# LED-PCB_DIG2.net
KiCad netlist of a schematic drawn in Altium Designer
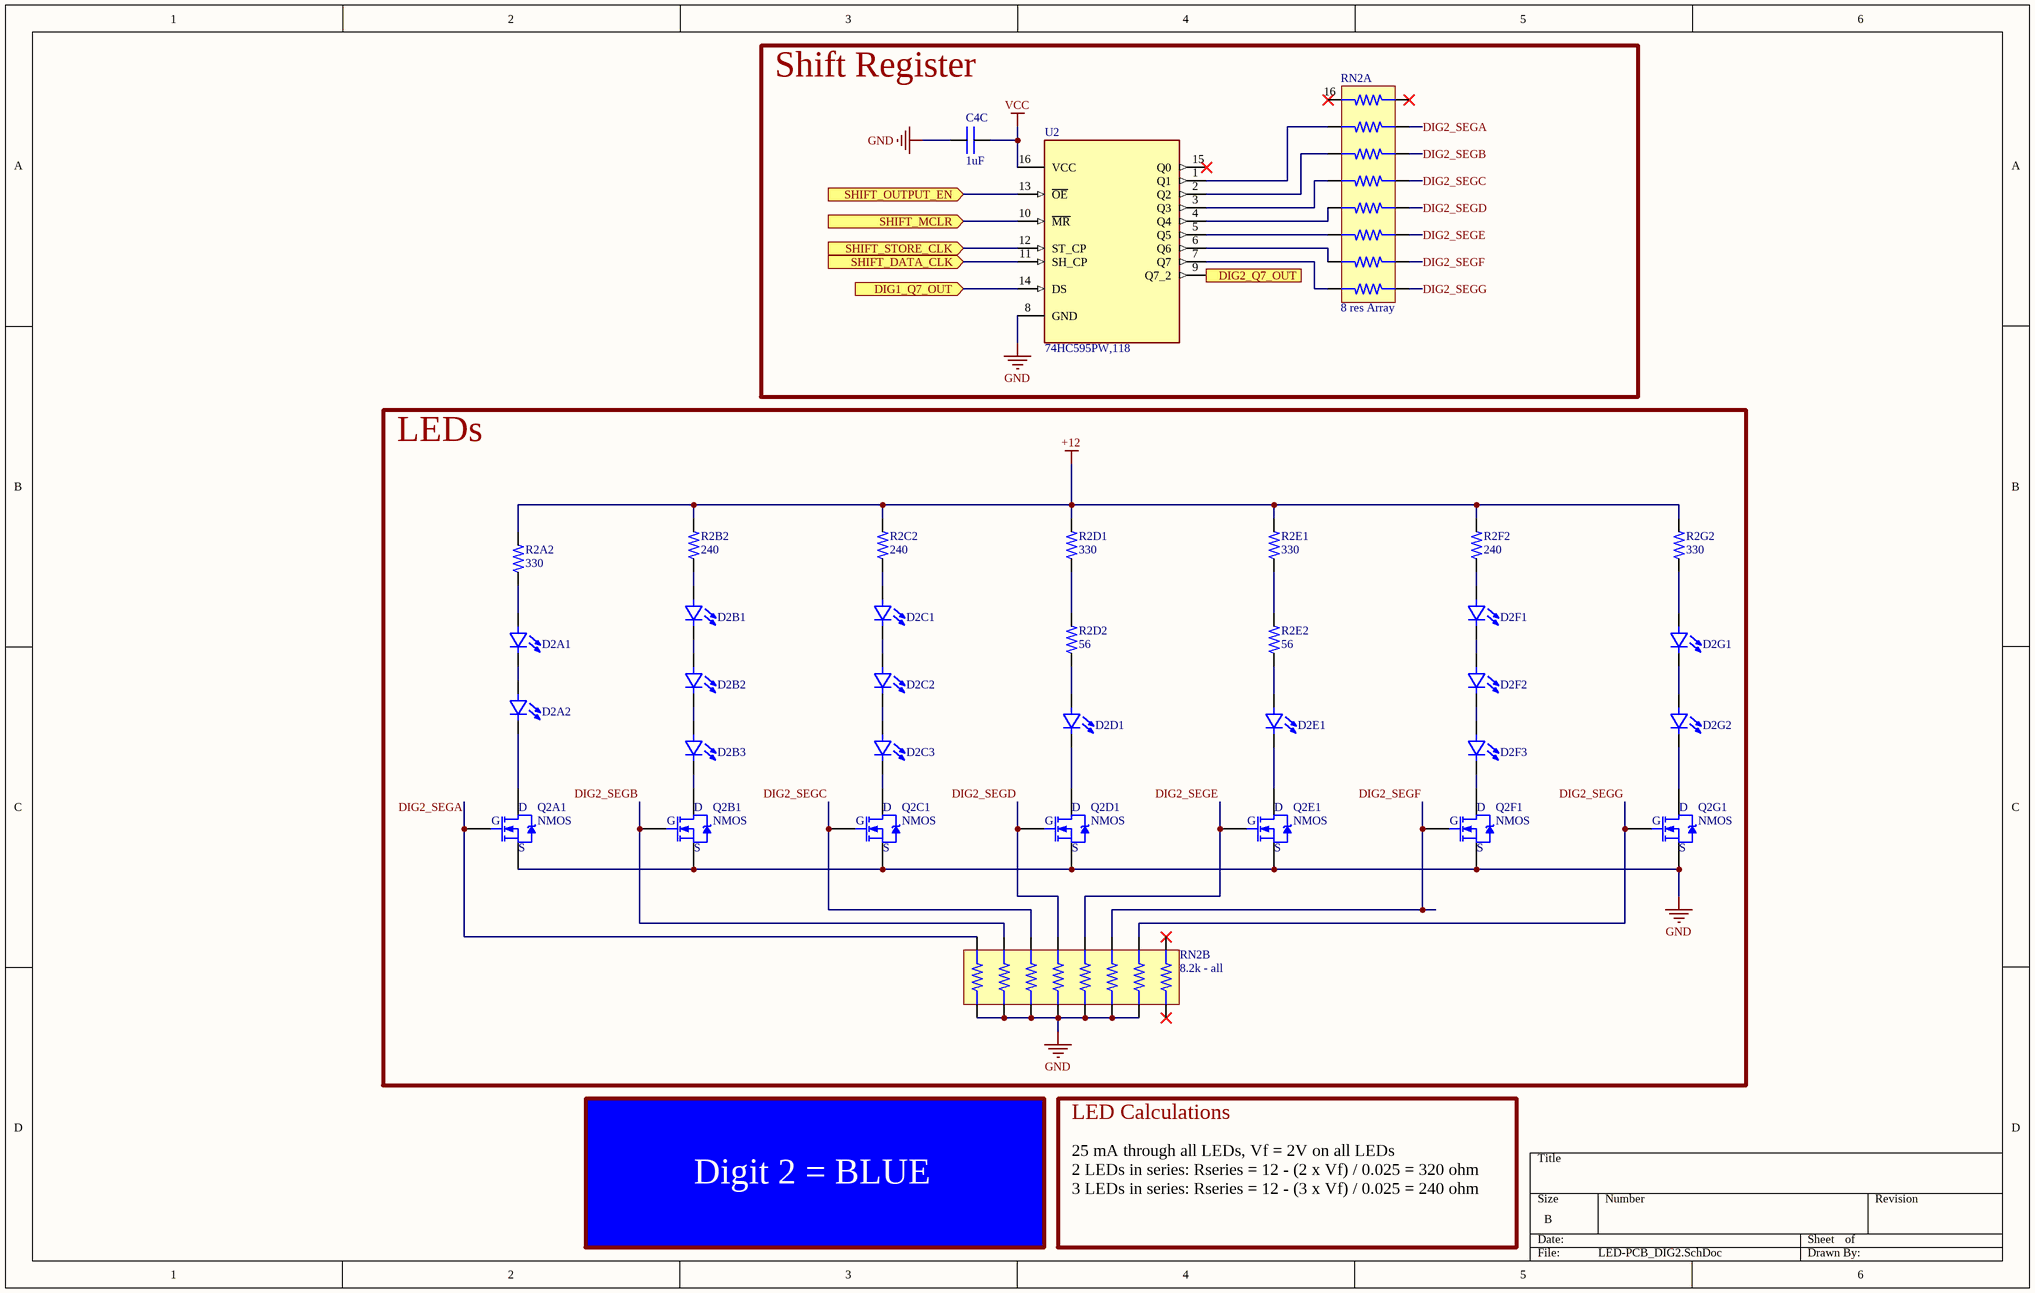
[diagram p0: LED-PCB_DIG2.SchDoc]

(export (version "E")
  (design (tool "Eeschema 10.0.6"))
  (components
    (comp (ref "C4C")
      (value "1uF")
      (footprint "sinking-clock:0402 CAP")
      (description "Capaicitor")
      (fields (field (name "MFR") "Samsung Microelectronics") (field (name "Comment") "CAP"))
      (libsource (lib "sinking-clock") (part "CAP"))
    )
    (comp (ref "D2A1")
      (value "LED - single")
      (footprint "sinking-clock:LED - 0603")
      (fields (field (name "MFR") "Wurth Elektronik"))
      (libsource (lib "sinking-clock") (part "LED - single"))
    )
    (comp (ref "D2A2")
      (value "LED - single")
      (footprint "sinking-clock:LED - 0603")
      (fields (field (name "MFR") "Wurth Elektronik"))
      (libsource (lib "sinking-clock") (part "LED - single"))
    )
    (comp (ref "D2B1")
      (value "LED - single")
      (footprint "sinking-clock:LED - 0603")
      (fields (field (name "MFR") "Wurth Elektronik"))
      (libsource (lib "sinking-clock") (part "LED - single"))
    )
    (comp (ref "D2B2")
      (value "LED - single")
      (footprint "sinking-clock:LED - 0603")
      (fields (field (name "MFR") "Wurth Elektronik"))
      (libsource (lib "sinking-clock") (part "LED - single"))
    )
    (comp (ref "D2B3")
      (value "LED - single")
      (footprint "sinking-clock:LED - 0603")
      (fields (field (name "MFR") "Wurth Elektronik"))
      (libsource (lib "sinking-clock") (part "LED - single"))
    )
    (comp (ref "D2C1")
      (value "LED - single")
      (footprint "sinking-clock:LED - 0603")
      (fields (field (name "MFR") "Wurth Elektronik"))
      (libsource (lib "sinking-clock") (part "LED - single"))
    )
    (comp (ref "D2C2")
      (value "LED - single")
      (footprint "sinking-clock:LED - 0603")
      (fields (field (name "MFR") "Wurth Elektronik"))
      (libsource (lib "sinking-clock") (part "LED - single"))
    )
    (comp (ref "D2C3")
      (value "LED - single")
      (footprint "sinking-clock:LED - 0603")
      (fields (field (name "MFR") "Wurth Elektronik"))
      (libsource (lib "sinking-clock") (part "LED - single"))
    )
    (comp (ref "D2D1")
      (value "LED - single")
      (footprint "sinking-clock:LED - 0603")
      (fields (field (name "MFR") "Wurth Elektronik"))
      (libsource (lib "sinking-clock") (part "LED - single"))
    )
    (comp (ref "D2E1")
      (value "LED - single")
      (footprint "sinking-clock:LED - 0603")
      (fields (field (name "MFR") "Wurth Elektronik"))
      (libsource (lib "sinking-clock") (part "LED - single"))
    )
    (comp (ref "D2F1")
      (value "LED - single")
      (footprint "sinking-clock:LED - 0603")
      (fields (field (name "MFR") "Wurth Elektronik"))
      (libsource (lib "sinking-clock") (part "LED - single"))
    )
    (comp (ref "D2F2")
      (value "LED - single")
      (footprint "sinking-clock:LED - 0603")
      (fields (field (name "MFR") "Wurth Elektronik"))
      (libsource (lib "sinking-clock") (part "LED - single"))
    )
    (comp (ref "D2F3")
      (value "LED - single")
      (footprint "sinking-clock:LED - 0603")
      (fields (field (name "MFR") "Wurth Elektronik"))
      (libsource (lib "sinking-clock") (part "LED - single"))
    )
    (comp (ref "D2G1")
      (value "LED - single")
      (footprint "sinking-clock:LED - 0603")
      (fields (field (name "MFR") "Wurth Elektronik"))
      (libsource (lib "sinking-clock") (part "LED - single"))
    )
    (comp (ref "D2G2")
      (value "LED - single")
      (footprint "sinking-clock:LED - 0603")
      (fields (field (name "MFR") "Wurth Elektronik"))
      (libsource (lib "sinking-clock") (part "LED - single"))
    )
    (comp (ref "Q2A1")
      (value "NMOS")
      (footprint "sinking-clock:SOT-23")
      (description "N-Channel MOSFET")
      (fields (field (name "MFR") "Diodes Incorporated"))
      (libsource (lib "sinking-clock") (part "NMOS"))
    )
    (comp (ref "Q2B1")
      (value "NMOS")
      (footprint "sinking-clock:SOT-23")
      (description "N-Channel MOSFET")
      (fields (field (name "MFR") "Diodes Incorporated"))
      (libsource (lib "sinking-clock") (part "NMOS"))
    )
    (comp (ref "Q2C1")
      (value "NMOS")
      (footprint "sinking-clock:SOT-23")
      (description "N-Channel MOSFET")
      (fields (field (name "MFR") "Diodes Incorporated"))
      (libsource (lib "sinking-clock") (part "NMOS"))
    )
    (comp (ref "Q2D1")
      (value "NMOS")
      (footprint "sinking-clock:SOT-23")
      (description "N-Channel MOSFET")
      (fields (field (name "MFR") "Diodes Incorporated"))
      (libsource (lib "sinking-clock") (part "NMOS"))
    )
    (comp (ref "Q2E1")
      (value "NMOS")
      (footprint "sinking-clock:SOT-23")
      (description "N-Channel MOSFET")
      (fields (field (name "MFR") "Diodes Incorporated"))
      (libsource (lib "sinking-clock") (part "NMOS"))
    )
    (comp (ref "Q2F1")
      (value "NMOS")
      (footprint "sinking-clock:SOT-23")
      (description "N-Channel MOSFET")
      (fields (field (name "MFR") "Diodes Incorporated"))
      (libsource (lib "sinking-clock") (part "NMOS"))
    )
    (comp (ref "Q2G1")
      (value "NMOS")
      (footprint "sinking-clock:SOT-23")
      (description "N-Channel MOSFET")
      (fields (field (name "MFR") "Diodes Incorporated"))
      (libsource (lib "sinking-clock") (part "NMOS"))
    )
    (comp (ref "R2A2")
      (value "330")
      (footprint "sinking-clock:0402 RES")
      (description "Resistor")
      (fields (field (name "MFR") "YAGEO") (field (name "Comment") "RES"))
      (libsource (lib "sinking-clock") (part "RES"))
    )
    (comp (ref "R2B2")
      (value "240")
      (footprint "sinking-clock:0402 RES")
      (description "Resistor")
      (fields (field (name "MFR") "YAGEO") (field (name "Comment") "RES"))
      (libsource (lib "sinking-clock") (part "RES"))
    )
    (comp (ref "R2C2")
      (value "240")
      (footprint "sinking-clock:0402 RES")
      (description "Resistor")
      (fields (field (name "MFR") "YAGEO") (field (name "Comment") "RES"))
      (libsource (lib "sinking-clock") (part "RES"))
    )
    (comp (ref "R2D1")
      (value "330")
      (footprint "sinking-clock:0402 RES")
      (description "Resistor")
      (fields (field (name "MFR") "YAGEO") (field (name "Comment") "RES"))
      (libsource (lib "sinking-clock") (part "RES"))
    )
    (comp (ref "R2D2")
      (value "56")
      (footprint "sinking-clock:0402 RES")
      (description "Resistor")
      (fields (field (name "PART NUMBER") "RC0402FR-0756RL") (field (name "Comment") "RES"))
      (libsource (lib "sinking-clock") (part "RES"))
    )
    (comp (ref "R2E1")
      (value "330")
      (footprint "sinking-clock:0402 RES")
      (description "Resistor")
      (fields (field (name "MFR") "YAGEO") (field (name "Comment") "RES"))
      (libsource (lib "sinking-clock") (part "RES"))
    )
    (comp (ref "R2E2")
      (value "56")
      (footprint "sinking-clock:0402 RES")
      (description "Resistor")
      (fields (field (name "PART NUMBER") "RC0402FR-0756RL") (field (name "Comment") "RES"))
      (libsource (lib "sinking-clock") (part "RES"))
    )
    (comp (ref "R2F2")
      (value "240")
      (footprint "sinking-clock:0402 RES")
      (description "Resistor")
      (fields (field (name "MFR") "YAGEO") (field (name "Comment") "RES"))
      (libsource (lib "sinking-clock") (part "RES"))
    )
    (comp (ref "R2G2")
      (value "330")
      (footprint "sinking-clock:0402 RES")
      (description "Resistor")
      (fields (field (name "MFR") "YAGEO") (field (name "Comment") "RES"))
      (libsource (lib "sinking-clock") (part "RES"))
    )
    (comp (ref "RN2A")
      (value "8 res Array")
      (footprint "sinking-clock:EXB2HV331JV")
      (fields (field (name "MFR") "Panasonic Microelectronics"))
      (libsource (lib "sinking-clock") (part "8 res Array"))
    )
    (comp (ref "RN2B")
      (value "8.2k - all")
      (footprint "sinking-clock:MNR18ERAPJ822")
      (fields (field (name "MFR") "Rohm Semiconductor"))
      (libsource (lib "sinking-clock") (part "MNR18ERAPJ822"))
    )
    (comp (ref "U2")
      (value "74HC595PW,118")
      (footprint "sinking-clock:16-TSSOP")
      (description "Shift Shift Register 1 Element 8 Bit 16-TSSOP")
      (libsource (lib "sinking-clock") (part "74HC595PW,118"))
    )
  )
  (nets
    (net (code "1") (name "+12") (class "Default")
      (node (ref "R2A2") (pin "2") (pinfunction "2_2") (pintype "passive"))
      (node (ref "R2B2") (pin "2") (pinfunction "2_2") (pintype "passive"))
      (node (ref "R2C2") (pin "2") (pinfunction "2_2") (pintype "passive"))
      (node (ref "R2D1") (pin "2") (pinfunction "2_2") (pintype "passive"))
      (node (ref "R2E1") (pin "2") (pinfunction "2_2") (pintype "passive"))
      (node (ref "R2F2") (pin "2") (pinfunction "2_2") (pintype "passive"))
      (node (ref "R2G2") (pin "2") (pinfunction "2_2") (pintype "passive"))
    )
    (net (code "2") (name "/DIG1_Q7_OUT") (class "Default")
      (node (ref "U2") (pin "14") (pinfunction "DS_14") (pintype "input"))
    )
    (net (code "3") (name "/DIG2_Q7_OUT") (class "Default")
      (node (ref "U2") (pin "9") (pinfunction "Q7_2_9") (pintype "output"))
    )
    (net (code "4") (name "/DIG2_SEGA") (class "Default")
      (node (ref "Q2A1") (pin "1") (pinfunction "G_1") (pintype "passive"))
      (node (ref "RN2A") (pin "2") (pinfunction "2_2") (pintype "passive"))
      (node (ref "RN2B") (pin "16") (pinfunction "16_16") (pintype "passive"))
    )
    (net (code "5") (name "/DIG2_SEGB") (class "Default")
      (node (ref "Q2B1") (pin "1") (pinfunction "G_1") (pintype "passive"))
      (node (ref "RN2A") (pin "3") (pinfunction "3_3") (pintype "passive"))
      (node (ref "RN2B") (pin "15") (pinfunction "15_15") (pintype "passive"))
    )
    (net (code "6") (name "/DIG2_SEGC") (class "Default")
      (node (ref "Q2C1") (pin "1") (pinfunction "G_1") (pintype "passive"))
      (node (ref "RN2A") (pin "4") (pinfunction "4_4") (pintype "passive"))
      (node (ref "RN2B") (pin "14") (pinfunction "14_14") (pintype "passive"))
    )
    (net (code "7") (name "/DIG2_SEGD") (class "Default")
      (node (ref "Q2D1") (pin "1") (pinfunction "G_1") (pintype "passive"))
      (node (ref "RN2A") (pin "5") (pinfunction "5_5") (pintype "passive"))
      (node (ref "RN2B") (pin "13") (pinfunction "13_13") (pintype "passive"))
    )
    (net (code "8") (name "/DIG2_SEGE") (class "Default")
      (node (ref "Q2E1") (pin "1") (pinfunction "G_1") (pintype "passive"))
      (node (ref "RN2A") (pin "6") (pinfunction "6_6") (pintype "passive"))
      (node (ref "RN2B") (pin "12") (pinfunction "12_12") (pintype "passive"))
    )
    (net (code "9") (name "/DIG2_SEGF") (class "Default")
      (node (ref "Q2F1") (pin "1") (pinfunction "G_1") (pintype "passive"))
      (node (ref "RN2A") (pin "7") (pinfunction "7_7") (pintype "passive"))
      (node (ref "RN2B") (pin "11") (pinfunction "11_11") (pintype "passive"))
    )
    (net (code "10") (name "/DIG2_SEGG") (class "Default")
      (node (ref "Q2G1") (pin "1") (pinfunction "G_1") (pintype "passive"))
      (node (ref "RN2A") (pin "8") (pinfunction "8_8") (pintype "passive"))
      (node (ref "RN2B") (pin "10") (pinfunction "10_10") (pintype "passive"))
    )
    (net (code "11") (name "/SHIFT_DATA_CLK") (class "Default")
      (node (ref "U2") (pin "11") (pinfunction "SH_CP_11") (pintype "input"))
    )
    (net (code "12") (name "/SHIFT_MCLR") (class "Default")
      (node (ref "U2") (pin "10") (pinfunction "~{MR}_10") (pintype "input"))
    )
    (net (code "13") (name "/SHIFT_OUTPUT_EN") (class "Default")
      (node (ref "U2") (pin "13") (pinfunction "~{OE}_13") (pintype "input"))
    )
    (net (code "14") (name "/SHIFT_STORE_CLK") (class "Default")
      (node (ref "U2") (pin "12") (pinfunction "ST_CP_12") (pintype "input"))
    )
    (net (code "15") (name "GND") (class "Default")
      (node (ref "C4C") (pin "1") (pinfunction "1_1") (pintype "passive"))
      (node (ref "Q2A1") (pin "2") (pinfunction "S_2") (pintype "passive"))
      (node (ref "Q2B1") (pin "2") (pinfunction "S_2") (pintype "passive"))
      (node (ref "Q2C1") (pin "2") (pinfunction "S_2") (pintype "passive"))
      (node (ref "Q2D1") (pin "2") (pinfunction "S_2") (pintype "passive"))
      (node (ref "Q2E1") (pin "2") (pinfunction "S_2") (pintype "passive"))
      (node (ref "Q2F1") (pin "2") (pinfunction "S_2") (pintype "passive"))
      (node (ref "Q2G1") (pin "2") (pinfunction "S_2") (pintype "passive"))
      (node (ref "RN2B") (pin "1") (pinfunction "1_1") (pintype "passive"))
      (node (ref "RN2B") (pin "2") (pinfunction "2_2") (pintype "passive"))
      (node (ref "RN2B") (pin "3") (pinfunction "3_3") (pintype "passive"))
      (node (ref "RN2B") (pin "4") (pinfunction "4_4") (pintype "passive"))
      (node (ref "RN2B") (pin "5") (pinfunction "5_5") (pintype "passive"))
      (node (ref "RN2B") (pin "6") (pinfunction "6_6") (pintype "passive"))
      (node (ref "RN2B") (pin "7") (pinfunction "7_7") (pintype "passive"))
      (node (ref "U2") (pin "8") (pinfunction "GND_8") (pintype "passive"))
    )
    (net (code "16") (name "Net-(D2A1-A)") (class "Default")
      (node (ref "D2A1") (pin "1") (pinfunction "A_1") (pintype "passive"))
      (node (ref "R2A2") (pin "1") (pinfunction "1_1") (pintype "passive"))
    )
    (net (code "17") (name "Net-(D2A1-C)") (class "Default")
      (node (ref "D2A1") (pin "2") (pinfunction "C_2") (pintype "passive"))
      (node (ref "D2A2") (pin "1") (pinfunction "A_1") (pintype "passive"))
    )
    (net (code "18") (name "Net-(D2A2-C)") (class "Default")
      (node (ref "D2A2") (pin "2") (pinfunction "C_2") (pintype "passive"))
      (node (ref "Q2A1") (pin "3") (pinfunction "D_3") (pintype "passive"))
    )
    (net (code "19") (name "Net-(D2B1-A)") (class "Default")
      (node (ref "D2B1") (pin "1") (pinfunction "A_1") (pintype "passive"))
      (node (ref "R2B2") (pin "1") (pinfunction "1_1") (pintype "passive"))
    )
    (net (code "20") (name "Net-(D2B1-C)") (class "Default")
      (node (ref "D2B1") (pin "2") (pinfunction "C_2") (pintype "passive"))
      (node (ref "D2B2") (pin "1") (pinfunction "A_1") (pintype "passive"))
    )
    (net (code "21") (name "Net-(D2B2-C)") (class "Default")
      (node (ref "D2B2") (pin "2") (pinfunction "C_2") (pintype "passive"))
      (node (ref "D2B3") (pin "1") (pinfunction "A_1") (pintype "passive"))
    )
    (net (code "22") (name "Net-(D2B3-C)") (class "Default")
      (node (ref "D2B3") (pin "2") (pinfunction "C_2") (pintype "passive"))
      (node (ref "Q2B1") (pin "3") (pinfunction "D_3") (pintype "passive"))
    )
    (net (code "23") (name "Net-(D2C1-A)") (class "Default")
      (node (ref "D2C1") (pin "1") (pinfunction "A_1") (pintype "passive"))
      (node (ref "R2C2") (pin "1") (pinfunction "1_1") (pintype "passive"))
    )
    (net (code "24") (name "Net-(D2C1-C)") (class "Default")
      (node (ref "D2C1") (pin "2") (pinfunction "C_2") (pintype "passive"))
      (node (ref "D2C2") (pin "1") (pinfunction "A_1") (pintype "passive"))
    )
    (net (code "25") (name "Net-(D2C2-C)") (class "Default")
      (node (ref "D2C2") (pin "2") (pinfunction "C_2") (pintype "passive"))
      (node (ref "D2C3") (pin "1") (pinfunction "A_1") (pintype "passive"))
    )
    (net (code "26") (name "Net-(D2C3-C)") (class "Default")
      (node (ref "D2C3") (pin "2") (pinfunction "C_2") (pintype "passive"))
      (node (ref "Q2C1") (pin "3") (pinfunction "D_3") (pintype "passive"))
    )
    (net (code "27") (name "Net-(D2D1-A)") (class "Default")
      (node (ref "D2D1") (pin "1") (pinfunction "A_1") (pintype "passive"))
      (node (ref "R2D2") (pin "1") (pinfunction "1_1") (pintype "passive"))
    )
    (net (code "28") (name "Net-(D2D1-C)") (class "Default")
      (node (ref "D2D1") (pin "2") (pinfunction "C_2") (pintype "passive"))
      (node (ref "Q2D1") (pin "3") (pinfunction "D_3") (pintype "passive"))
    )
    (net (code "29") (name "Net-(D2E1-A)") (class "Default")
      (node (ref "D2E1") (pin "1") (pinfunction "A_1") (pintype "passive"))
      (node (ref "R2E2") (pin "1") (pinfunction "1_1") (pintype "passive"))
    )
    (net (code "30") (name "Net-(D2E1-C)") (class "Default")
      (node (ref "D2E1") (pin "2") (pinfunction "C_2") (pintype "passive"))
      (node (ref "Q2E1") (pin "3") (pinfunction "D_3") (pintype "passive"))
    )
    (net (code "31") (name "Net-(D2F1-A)") (class "Default")
      (node (ref "D2F1") (pin "1") (pinfunction "A_1") (pintype "passive"))
      (node (ref "R2F2") (pin "1") (pinfunction "1_1") (pintype "passive"))
    )
    (net (code "32") (name "Net-(D2F1-C)") (class "Default")
      (node (ref "D2F1") (pin "2") (pinfunction "C_2") (pintype "passive"))
      (node (ref "D2F2") (pin "1") (pinfunction "A_1") (pintype "passive"))
    )
    (net (code "33") (name "Net-(D2F2-C)") (class "Default")
      (node (ref "D2F2") (pin "2") (pinfunction "C_2") (pintype "passive"))
      (node (ref "D2F3") (pin "1") (pinfunction "A_1") (pintype "passive"))
    )
    (net (code "34") (name "Net-(D2F3-C)") (class "Default")
      (node (ref "D2F3") (pin "2") (pinfunction "C_2") (pintype "passive"))
      (node (ref "Q2F1") (pin "3") (pinfunction "D_3") (pintype "passive"))
    )
    (net (code "35") (name "Net-(D2G1-A)") (class "Default")
      (node (ref "D2G1") (pin "1") (pinfunction "A_1") (pintype "passive"))
      (node (ref "R2G2") (pin "1") (pinfunction "1_1") (pintype "passive"))
    )
    (net (code "36") (name "Net-(D2G1-C)") (class "Default")
      (node (ref "D2G1") (pin "2") (pinfunction "C_2") (pintype "passive"))
      (node (ref "D2G2") (pin "1") (pinfunction "A_1") (pintype "passive"))
    )
    (net (code "37") (name "Net-(D2G2-C)") (class "Default")
      (node (ref "D2G2") (pin "2") (pinfunction "C_2") (pintype "passive"))
      (node (ref "Q2G1") (pin "3") (pinfunction "D_3") (pintype "passive"))
    )
    (net (code "38") (name "Net-(R2D1-Pad1)") (class "Default")
      (node (ref "R2D1") (pin "1") (pinfunction "1_1") (pintype "passive"))
      (node (ref "R2D2") (pin "2") (pinfunction "2_2") (pintype "passive"))
    )
    (net (code "39") (name "Net-(R2E1-Pad1)") (class "Default")
      (node (ref "R2E1") (pin "1") (pinfunction "1_1") (pintype "passive"))
      (node (ref "R2E2") (pin "2") (pinfunction "2_2") (pintype "passive"))
    )
    (net (code "40") (name "Net-(U2-Q1)") (class "Default")
      (node (ref "RN2A") (pin "15") (pinfunction "15_15") (pintype "passive"))
      (node (ref "U2") (pin "1") (pinfunction "Q1_1") (pintype "output"))
    )
    (net (code "41") (name "Net-(U2-Q2)") (class "Default")
      (node (ref "RN2A") (pin "14") (pinfunction "14_14") (pintype "passive"))
      (node (ref "U2") (pin "2") (pinfunction "Q2_2") (pintype "output"))
    )
    (net (code "42") (name "Net-(U2-Q3)") (class "Default")
      (node (ref "RN2A") (pin "13") (pinfunction "13_13") (pintype "passive"))
      (node (ref "U2") (pin "3") (pinfunction "Q3_3") (pintype "output"))
    )
    (net (code "43") (name "Net-(U2-Q4)") (class "Default")
      (node (ref "RN2A") (pin "12") (pinfunction "12_12") (pintype "passive"))
      (node (ref "U2") (pin "4") (pinfunction "Q4_4") (pintype "output"))
    )
    (net (code "44") (name "Net-(U2-Q5)") (class "Default")
      (node (ref "RN2A") (pin "11") (pinfunction "11_11") (pintype "passive"))
      (node (ref "U2") (pin "5") (pinfunction "Q5_5") (pintype "output"))
    )
    (net (code "45") (name "Net-(U2-Q6)") (class "Default")
      (node (ref "RN2A") (pin "10") (pinfunction "10_10") (pintype "passive"))
      (node (ref "U2") (pin "6") (pinfunction "Q6_6") (pintype "output"))
    )
    (net (code "46") (name "Net-(U2-Q7)") (class "Default")
      (node (ref "RN2A") (pin "9") (pinfunction "9_9") (pintype "passive"))
      (node (ref "U2") (pin "7") (pinfunction "Q7_7") (pintype "output"))
    )
    (net (code "47") (name "VCC") (class "Default")
      (node (ref "C4C") (pin "2") (pinfunction "2_2") (pintype "passive"))
      (node (ref "U2") (pin "16") (pinfunction "VCC_16") (pintype "power_in"))
    )
    (net (code "48") (name "unconnected-(RN2A-Pad1)") (class "Default")
      (node (ref "RN2A") (pin "1") (pinfunction "1_1") (pintype "passive+no_connect"))
    )
    (net (code "49") (name "unconnected-(RN2A-Pad16)") (class "Default")
      (node (ref "RN2A") (pin "16") (pinfunction "16_16") (pintype "passive+no_connect"))
    )
    (net (code "50") (name "unconnected-(RN2B-Pad8)") (class "Default")
      (node (ref "RN2B") (pin "8") (pinfunction "8_8") (pintype "passive+no_connect"))
    )
    (net (code "51") (name "unconnected-(RN2B-Pad9)") (class "Default")
      (node (ref "RN2B") (pin "9") (pinfunction "9_9") (pintype "passive+no_connect"))
    )
    (net (code "52") (name "unconnected-(U2-Q0-Pad15)") (class "Default")
      (node (ref "U2") (pin "15") (pinfunction "Q0_15") (pintype "output+no_connect"))
    )
  )
)
